# doodle_with_clock5_atmega328_3.net
KiCad netlist of a schematic drawn in EAGLE
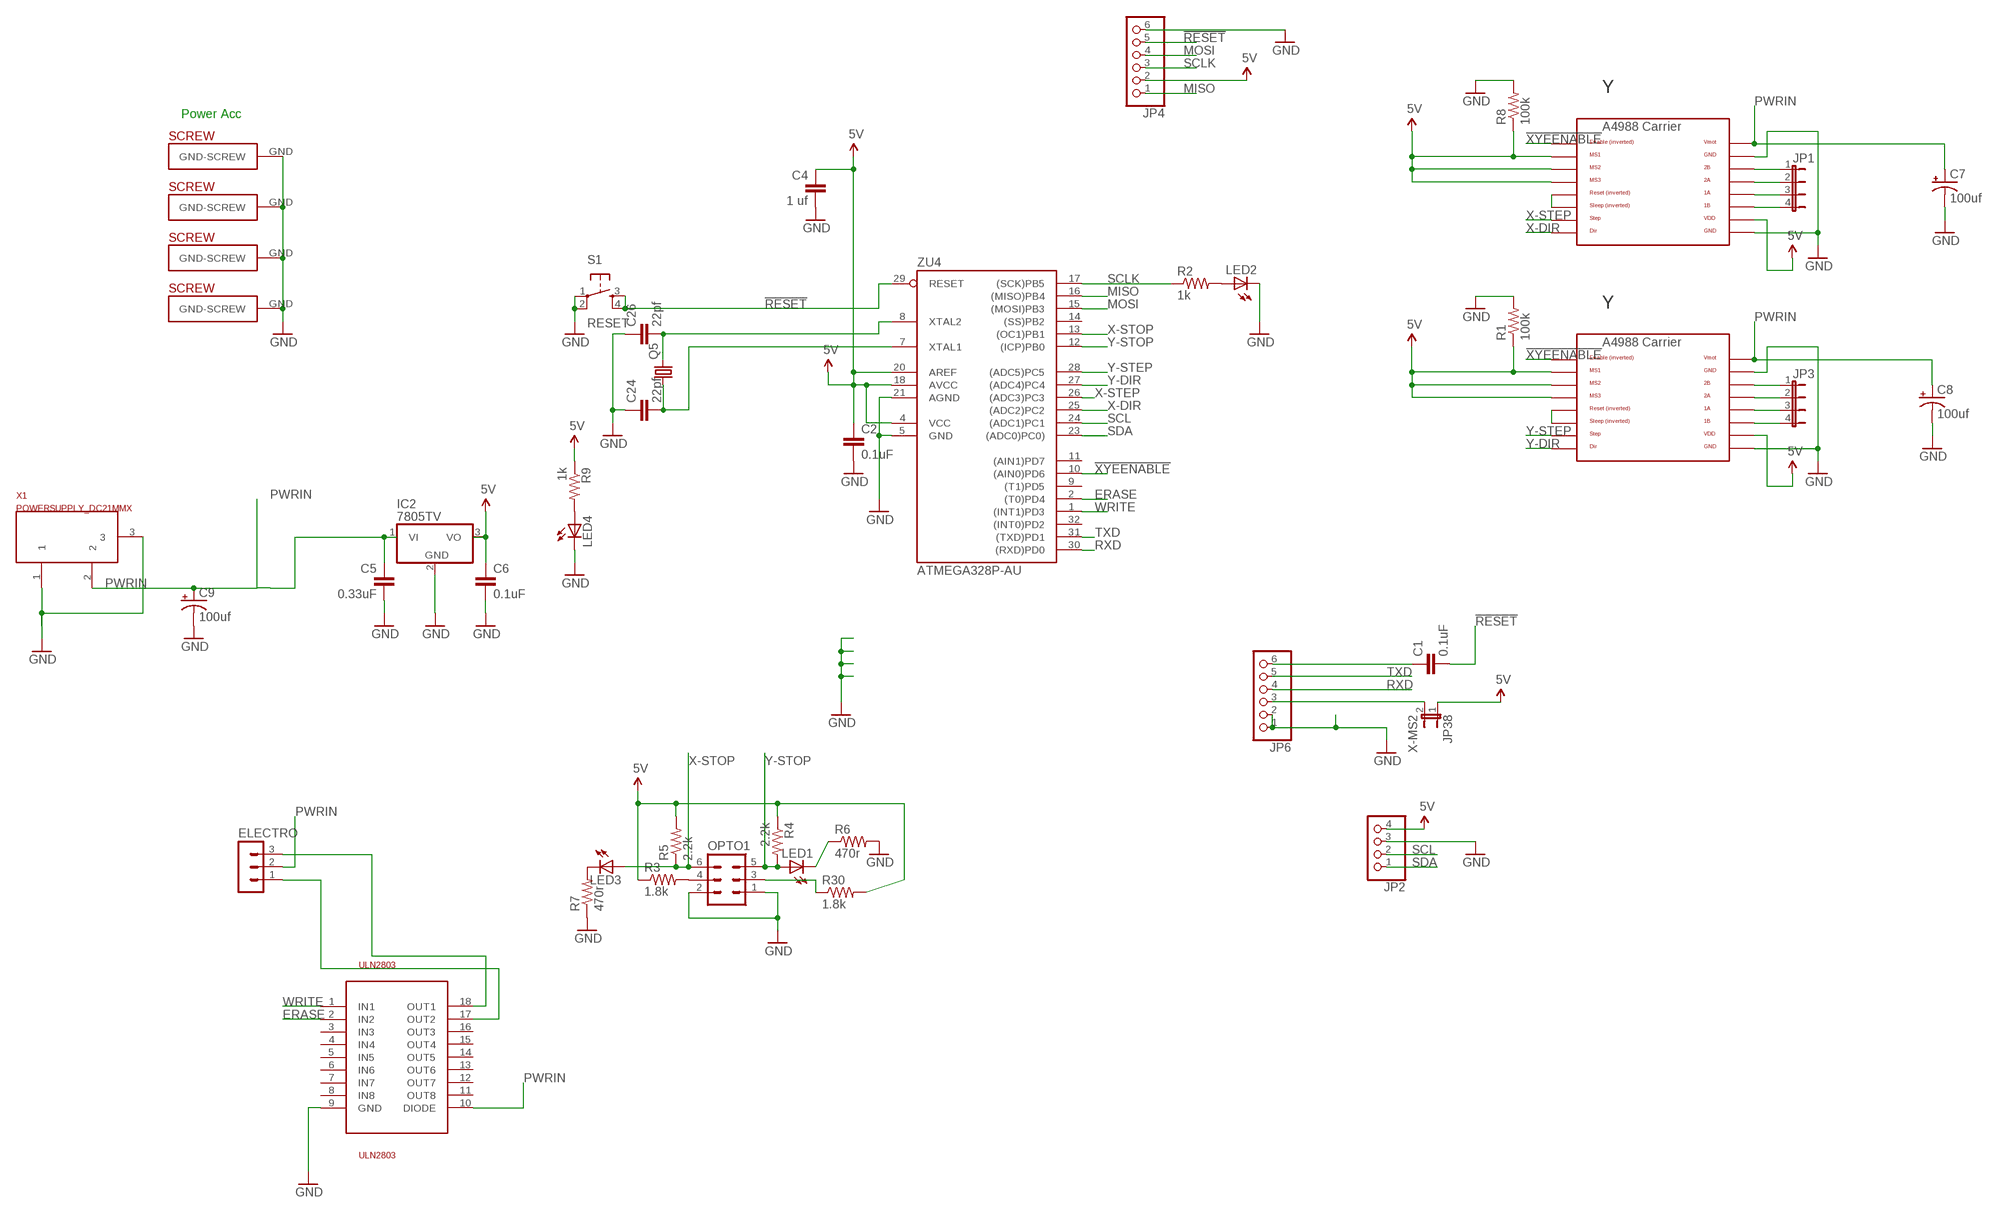
[diagram p0: schematic, sheet 1, part 1 of 2]
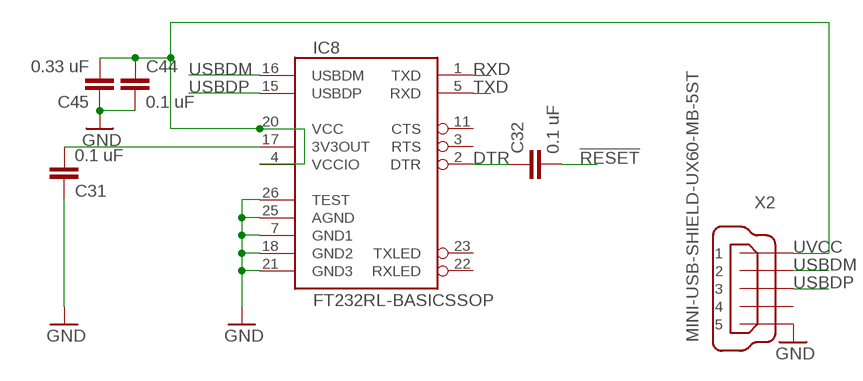
[diagram p1: schematic, sheet 1, part 2 of 2]

(export (version "E")
  (design (tool "Eeschema 10.0.6"))
  (components
    (comp (ref "C1")
      (value "0.1uF")
      (footprint "eagle-import:0805")
      (libsource (lib "eagle-import") (part "CAP0805"))
    )
    (comp (ref "C2")
      (value "0.1uF")
      (footprint "eagle-import:0805")
      (libsource (lib "eagle-import") (part "CAP0805"))
    )
    (comp (ref "C4")
      (value "1 uf")
      (footprint "eagle-import:0805")
      (libsource (lib "eagle-import") (part "CAP0805"))
    )
    (comp (ref "C5")
      (value "0.33uF")
      (footprint "eagle-import:CAP-PTH-SMALL2")
      (libsource (lib "eagle-import") (part "CAPPTH2"))
    )
    (comp (ref "C6")
      (value "0.1uF")
      (footprint "eagle-import:CAP-PTH-SMALL2")
      (libsource (lib "eagle-import") (part "CAPPTH2"))
    )
    (comp (ref "C7")
      (value "100uf")
      (footprint "eagle-import:CPOL-RADIAL-100UF-25V")
      (libsource (lib "eagle-import") (part "CAP_POLPTH1"))
    )
    (comp (ref "C8")
      (value "100uf")
      (footprint "eagle-import:CPOL-RADIAL-100UF-25V")
      (libsource (lib "eagle-import") (part "CAP_POLPTH1"))
    )
    (comp (ref "C9")
      (value "100uf")
      (footprint "eagle-import:CPOL-RADIAL-100UF-25V")
      (libsource (lib "eagle-import") (part "CAP_POLPTH1"))
    )
    (comp (ref "C24")
      (value "22pf")
      (footprint "eagle-import:0805")
      (libsource (lib "eagle-import") (part "CAP0805"))
    )
    (comp (ref "C26")
      (value "22pf")
      (footprint "eagle-import:0805")
      (libsource (lib "eagle-import") (part "CAP0805"))
    )
    (comp (ref "C31")
      (value "0.1 uF")
      (footprint "eagle-import:C1206")
      (libsource (lib "eagle-import") (part "C-EUC1206"))
    )
    (comp (ref "C32")
      (value "0.1 uF")
      (footprint "eagle-import:C1206")
      (libsource (lib "eagle-import") (part "C-EUC1206"))
    )
    (comp (ref "C44")
      (value "0.1 uF")
      (footprint "eagle-import:C1206")
      (libsource (lib "eagle-import") (part "C-EUC1206"))
    )
    (comp (ref "C45")
      (value "0.33 uF")
      (footprint "eagle-import:C1206")
      (libsource (lib "eagle-import") (part "C-EUC1206"))
    )
    (comp (ref "ELECTRO")
      (value "MA03-1")
      (footprint "eagle-import:MA03-1")
      (libsource (lib "eagle-import") (part "MA03-1"))
    )
    (comp (ref "IC2")
      (value "7805TV")
      (footprint "eagle-import:TO220V")
      (libsource (lib "eagle-import") (part "78TV05"))
    )
    (comp (ref "IC8")
      (value "FT232RL-BASICSSOP")
      (footprint "eagle-import:SSOP28DB")
      (libsource (lib "eagle-import") (part "FT232RL-BASICSSOP"))
    )
    (comp (ref "JP1")
      (value "JP4E")
      (footprint "eagle-import:JP4")
      (libsource (lib "eagle-import") (part "JP4E"))
    )
    (comp (ref "JP2")
      (value "PINHD-1X4")
      (footprint "eagle-import:1X04")
      (libsource (lib "eagle-import") (part "PINHD-1X4"))
    )
    (comp (ref "JP3")
      (value "JP4E")
      (footprint "eagle-import:JP4")
      (libsource (lib "eagle-import") (part "JP4E"))
    )
    (comp (ref "JP4")
      (value "PINHD-1X6/90")
      (footprint "eagle-import:1X06_90")
      (libsource (lib "eagle-import") (part "PINHD-1X6/90"))
    )
    (comp (ref "JP6")
      (value "PINHD-1X6")
      (footprint "eagle-import:1X06")
      (libsource (lib "eagle-import") (part "PINHD-1X6"))
    )
    (comp (ref "JP38")
      (value "X-MS2")
      (footprint "eagle-import:1X02")
      (libsource (lib "eagle-import") (part "JUMPER-2PTH"))
    )
    (comp (ref "LED1")
      (value "LEDCHIPLED_0805")
      (footprint "eagle-import:CHIPLED_0805")
      (libsource (lib "eagle-import") (part "LEDCHIPLED_0805"))
    )
    (comp (ref "LED2")
      (value "LEDCHIPLED_0805")
      (footprint "eagle-import:CHIPLED_0805")
      (libsource (lib "eagle-import") (part "LEDCHIPLED_0805"))
    )
    (comp (ref "LED3")
      (value "LEDCHIPLED_0805")
      (footprint "eagle-import:CHIPLED_0805")
      (libsource (lib "eagle-import") (part "LEDCHIPLED_0805"))
    )
    (comp (ref "LED4")
      (value "LEDCHIPLED_0805")
      (footprint "eagle-import:CHIPLED_0805")
      (libsource (lib "eagle-import") (part "LEDCHIPLED_0805"))
    )
    (comp (ref "OPTO1")
      (value "MA03-2")
      (footprint "eagle-import:MA03-2")
      (libsource (lib "eagle-import") (part "MA03-2"))
    )
    (comp (ref "Q5")
      (value "CRYSTALHC49S")
      (footprint "eagle-import:HC49_S")
      (libsource (lib "eagle-import") (part "CRYSTALHC49S"))
    )
    (comp (ref "R1")
      (value "100k")
      (footprint "eagle-import:0207_7")
      (libsource (lib "eagle-import") (part "R-US_0207/7"))
    )
    (comp (ref "R2")
      (value "1k")
      (footprint "eagle-import:R0805")
      (libsource (lib "eagle-import") (part "resistor_R-US_R0805"))
    )
    (comp (ref "R3")
      (value "1.8k")
      (footprint "eagle-import:R0805")
      (libsource (lib "eagle-import") (part "resistor_R-US_R0805"))
    )
    (comp (ref "R4")
      (value "2.2k")
      (footprint "eagle-import:R0805")
      (libsource (lib "eagle-import") (part "resistor_R-US_R0805"))
    )
    (comp (ref "R5")
      (value "2.2k")
      (footprint "eagle-import:R0805")
      (libsource (lib "eagle-import") (part "resistor_R-US_R0805"))
    )
    (comp (ref "R6")
      (value "470r")
      (footprint "eagle-import:R0805")
      (libsource (lib "eagle-import") (part "resistor_R-US_R0805"))
    )
    (comp (ref "R7")
      (value "470r")
      (footprint "eagle-import:R0805")
      (libsource (lib "eagle-import") (part "resistor_R-US_R0805"))
    )
    (comp (ref "R8")
      (value "100k")
      (footprint "eagle-import:0207_7")
      (libsource (lib "eagle-import") (part "R-US_0207/7"))
    )
    (comp (ref "R9")
      (value "1k")
      (footprint "eagle-import:R0805")
      (libsource (lib "eagle-import") (part "resistor_R-US_R0805"))
    )
    (comp (ref "R30")
      (value "1.8k")
      (footprint "eagle-import:R0603")
      (libsource (lib "eagle-import") (part "resistor_R-US_R0603"))
    )
    (comp (ref "S1")
      (value "RESET")
      (footprint "eagle-import:TACTILE-PTH")
      (libsource (lib "eagle-import") (part "TAC_SWITCHPTH"))
    )
    (comp (ref "U$1")
      (value "A4988BREAKOUT")
      (footprint "eagle-import:A4988BREAKOUT")
      (libsource (lib "eagle-import") (part "A4988BREAKOUT"))
    )
    (comp (ref "U$7")
      (value "A4988BREAKOUT")
      (footprint "eagle-import:A4988BREAKOUT")
      (libsource (lib "eagle-import") (part "A4988BREAKOUT"))
    )
    (comp (ref "U$14")
      (value "PLATED-SCREW")
      (footprint "eagle-import:PLATEDSCREW")
      (libsource (lib "eagle-import") (part "PLATED-SCREW"))
    )
    (comp (ref "U$17")
      (value "PLATED-SCREW")
      (footprint "eagle-import:PLATEDSCREW")
      (libsource (lib "eagle-import") (part "PLATED-SCREW"))
    )
    (comp (ref "U$18")
      (value "PLATED-SCREW")
      (footprint "eagle-import:PLATEDSCREW")
      (libsource (lib "eagle-import") (part "PLATED-SCREW"))
    )
    (comp (ref "U$38")
      (value "PLATED-SCREW")
      (footprint "eagle-import:PLATEDSCREW")
      (libsource (lib "eagle-import") (part "PLATED-SCREW"))
    )
    (comp (ref "ULN2803")
      (value "ULN2803")
      (footprint "eagle-import:SO18L")
      (libsource (lib "eagle-import") (part "ULN2803"))
    )
    (comp (ref "X1")
      (value "POWERSUPPLY_DC21MMX")
      (footprint "eagle-import:POWERSUPPLY_DC-21MM")
      (libsource (lib "eagle-import") (part "POWERSUPPLY_DC21MMX"))
    )
    (comp (ref "X2")
      (value "MINI-USB-SHIELD-UX60-MB-5ST")
      (footprint "eagle-import:UX60-MB-5ST")
      (libsource (lib "eagle-import") (part "MINI-USB-SHIELD-UX60-MB-5ST"))
    )
    (comp (ref "ZU4")
      (value "ATMEGA328P-AU")
      (footprint "eagle-import:TQFP32-08")
      (libsource (lib "eagle-import") (part "ATMEGA328P-AU"))
    )
  )
  (nets
    (net (code "1") (name "/DTR") (class "Default")
      (node (ref "C32") (pin "1") (pinfunction "1_1") (pintype "passive"))
      (node (ref "IC8") (pin "2") (pinfunction "DTR_2") (pintype "bidirectional"))
    )
    (net (code "2") (name "/ERASE") (class "Default")
      (node (ref "ULN2803") (pin "2") (pinfunction "IN2_2") (pintype "input"))
      (node (ref "ZU4") (pin "2") (pinfunction "(T0)PD4_2") (pintype "bidirectional"))
    )
    (net (code "3") (name "/MISO") (class "Default")
      (node (ref "JP4") (pin "1") (pinfunction "1_1") (pintype "passive"))
      (node (ref "ZU4") (pin "16") (pinfunction "(MISO)PB4_16") (pintype "bidirectional"))
    )
    (net (code "4") (name "/MOSI") (class "Default")
      (node (ref "JP4") (pin "4") (pinfunction "4_4") (pintype "passive"))
      (node (ref "ZU4") (pin "15") (pinfunction "(MOSI)PB3_15") (pintype "bidirectional"))
    )
    (net (code "5") (name "/PWRIN") (class "Default")
      (node (ref "C5") (pin "1") (pinfunction "1_1") (pintype "passive"))
      (node (ref "C7") (pin "1") (pinfunction "+_1") (pintype "passive"))
      (node (ref "C8") (pin "1") (pinfunction "+_1") (pintype "passive"))
      (node (ref "C9") (pin "1") (pinfunction "+_1") (pintype "passive"))
      (node (ref "ELECTRO") (pin "2") (pinfunction "2_2") (pintype "passive"))
      (node (ref "IC2") (pin "1") (pinfunction "VI_1") (pintype "input"))
      (node (ref "U$1") (pin "VMOT") (pinfunction "VMOT_VMOT") (pintype "power_in"))
      (node (ref "U$7") (pin "VMOT") (pinfunction "VMOT_VMOT") (pintype "power_in"))
      (node (ref "ULN2803") (pin "10") (pinfunction "DIODE_10") (pintype "power_in"))
      (node (ref "X1") (pin "2") (pinfunction "2_2") (pintype "power_in"))
    )
    (net (code "6") (name "/RXD") (class "Default")
      (node (ref "IC8") (pin "1") (pinfunction "TXD_1") (pintype "output"))
      (node (ref "JP6") (pin "4") (pinfunction "4_4") (pintype "passive"))
      (node (ref "ZU4") (pin "30") (pinfunction "(RXD)PD0_30") (pintype "bidirectional"))
    )
    (net (code "7") (name "/SCL") (class "Default")
      (node (ref "JP2") (pin "2") (pinfunction "2_2") (pintype "passive"))
      (node (ref "ZU4") (pin "24") (pinfunction "(ADC1)PC1_24") (pintype "bidirectional"))
    )
    (net (code "8") (name "/SCLK") (class "Default")
      (node (ref "JP4") (pin "3") (pinfunction "3_3") (pintype "passive"))
      (node (ref "R2") (pin "1") (pinfunction "1_1") (pintype "passive"))
      (node (ref "ZU4") (pin "17") (pinfunction "(SCK)PB5_17") (pintype "bidirectional"))
    )
    (net (code "9") (name "/SDA") (class "Default")
      (node (ref "JP2") (pin "1") (pinfunction "1_1") (pintype "passive"))
      (node (ref "ZU4") (pin "23") (pinfunction "(ADC0)PC0)_23") (pintype "bidirectional"))
    )
    (net (code "10") (name "/TXD") (class "Default")
      (node (ref "IC8") (pin "5") (pinfunction "RXD_5") (pintype "input"))
      (node (ref "JP6") (pin "5") (pinfunction "5_5") (pintype "passive"))
      (node (ref "ZU4") (pin "31") (pinfunction "(TXD)PD1_31") (pintype "bidirectional"))
    )
    (net (code "11") (name "/USBDM") (class "Default")
      (node (ref "IC8") (pin "16") (pinfunction "USBDM_16") (pintype "bidirectional"))
      (node (ref "X2") (pin "2") (pinfunction "2_2") (pintype "input"))
    )
    (net (code "12") (name "/USBDP") (class "Default")
      (node (ref "IC8") (pin "15") (pinfunction "USBDP_15") (pintype "bidirectional"))
      (node (ref "X2") (pin "3") (pinfunction "3_3") (pintype "input"))
    )
    (net (code "13") (name "/UVCC") (class "Default")
      (node (ref "C44") (pin "1") (pinfunction "1_1") (pintype "passive"))
      (node (ref "C45") (pin "2") (pinfunction "2_2") (pintype "passive"))
      (node (ref "IC8") (pin "20") (pinfunction "VCC_20") (pintype "power_in"))
      (node (ref "IC8") (pin "4") (pinfunction "VCCIO_4") (pintype "power_in"))
      (node (ref "X2") (pin "1") (pinfunction "1_1") (pintype "input"))
    )
    (net (code "14") (name "/WRITE") (class "Default")
      (node (ref "ULN2803") (pin "1") (pinfunction "IN1_1") (pintype "input"))
      (node (ref "ZU4") (pin "1") (pinfunction "(INT1)PD3_1") (pintype "bidirectional"))
    )
    (net (code "15") (name "/X-DIR") (class "Default")
      (node (ref "U$7") (pin "DIR") (pinfunction "DIR_DIR") (pintype "input"))
      (node (ref "ZU4") (pin "25") (pinfunction "(ADC2)PC2_25") (pintype "bidirectional"))
    )
    (net (code "16") (name "/X-STEP") (class "Default")
      (node (ref "U$7") (pin "STEP") (pinfunction "STEP_STEP") (pintype "input"))
      (node (ref "ZU4") (pin "26") (pinfunction "(ADC3)PC3_26") (pintype "bidirectional"))
    )
    (net (code "17") (name "/X-STOP") (class "Default")
      (node (ref "LED3") (pin "A") (pinfunction "A_A") (pintype "passive"))
      (node (ref "OPTO1") (pin "6") (pinfunction "6_6") (pintype "passive"))
      (node (ref "R5") (pin "1") (pinfunction "1_1") (pintype "passive"))
      (node (ref "ZU4") (pin "13") (pinfunction "(OC1)PB1_13") (pintype "bidirectional"))
    )
    (net (code "18") (name "/Y-DIR") (class "Default")
      (node (ref "U$1") (pin "DIR") (pinfunction "DIR_DIR") (pintype "input"))
      (node (ref "ZU4") (pin "27") (pinfunction "(ADC4)PC4_27") (pintype "bidirectional"))
    )
    (net (code "19") (name "/Y-STEP") (class "Default")
      (node (ref "U$1") (pin "STEP") (pinfunction "STEP_STEP") (pintype "input"))
      (node (ref "ZU4") (pin "28") (pinfunction "(ADC5)PC5_28") (pintype "bidirectional"))
    )
    (net (code "20") (name "/Y-STOP") (class "Default")
      (node (ref "LED1") (pin "A") (pinfunction "A_A") (pintype "passive"))
      (node (ref "OPTO1") (pin "5") (pinfunction "5_5") (pintype "passive"))
      (node (ref "R4") (pin "2") (pinfunction "2_2") (pintype "passive"))
      (node (ref "ZU4") (pin "12") (pinfunction "(ICP)PB0_12") (pintype "bidirectional"))
    )
    (net (code "21") (name "/~{RESET}") (class "Default")
      (node (ref "C1") (pin "2") (pinfunction "2_2") (pintype "passive"))
      (node (ref "C32") (pin "2") (pinfunction "2_2") (pintype "passive"))
      (node (ref "JP4") (pin "5") (pinfunction "5_5") (pintype "passive"))
      (node (ref "S1") (pin "3") (pinfunction "3_3") (pintype "passive"))
      (node (ref "S1") (pin "4") (pinfunction "4_4") (pintype "passive"))
      (node (ref "ZU4") (pin "29") (pinfunction "RESET_29") (pintype "input"))
    )
    (net (code "22") (name "/~{XYEENABLE}") (class "Default")
      (node (ref "U$1") (pin "EN") (pinfunction "EN_EN") (pintype "input"))
      (node (ref "U$7") (pin "EN") (pinfunction "EN_EN") (pintype "input"))
      (node (ref "ZU4") (pin "10") (pinfunction "(AIN0)PD6_10") (pintype "bidirectional"))
    )
    (net (code "23") (name "5V") (class "Default")
      (node (ref "C2") (pin "1") (pinfunction "1_1") (pintype "passive"))
      (node (ref "C4") (pin "1") (pinfunction "1_1") (pintype "passive"))
      (node (ref "C6") (pin "1") (pinfunction "1_1") (pintype "passive"))
      (node (ref "IC2") (pin "3") (pinfunction "VO_3") (pintype "passive"))
      (node (ref "JP2") (pin "4") (pinfunction "4_4") (pintype "passive"))
      (node (ref "JP38") (pin "1") (pinfunction "1_1") (pintype "passive"))
      (node (ref "JP4") (pin "2") (pinfunction "2_2") (pintype "passive"))
      (node (ref "R1") (pin "1") (pinfunction "1_1") (pintype "passive"))
      (node (ref "R3") (pin "1") (pinfunction "1_1") (pintype "passive"))
      (node (ref "R30") (pin "2") (pinfunction "2_2") (pintype "passive"))
      (node (ref "R4") (pin "1") (pinfunction "1_1") (pintype "passive"))
      (node (ref "R5") (pin "2") (pinfunction "2_2") (pintype "passive"))
      (node (ref "R8") (pin "1") (pinfunction "1_1") (pintype "passive"))
      (node (ref "R9") (pin "1") (pinfunction "1_1") (pintype "passive"))
      (node (ref "U$1") (pin "MS1") (pinfunction "MS1_MS1") (pintype "input"))
      (node (ref "U$1") (pin "MS2") (pinfunction "MS2_MS2") (pintype "input"))
      (node (ref "U$1") (pin "MS3") (pinfunction "MS3_MS3") (pintype "input"))
      (node (ref "U$1") (pin "VDD") (pinfunction "VDD_VDD") (pintype "power_in"))
      (node (ref "U$7") (pin "MS1") (pinfunction "MS1_MS1") (pintype "input"))
      (node (ref "U$7") (pin "MS2") (pinfunction "MS2_MS2") (pintype "input"))
      (node (ref "U$7") (pin "MS3") (pinfunction "MS3_MS3") (pintype "input"))
      (node (ref "U$7") (pin "VDD") (pinfunction "VDD_VDD") (pintype "power_in"))
      (node (ref "ZU4") (pin "18") (pinfunction "AVCC_18") (pintype "power_in"))
      (node (ref "ZU4") (pin "20") (pinfunction "AREF_20") (pintype "passive"))
      (node (ref "ZU4") (pin "4") (pinfunction "VCC_4") (pintype "power_in"))
    )
    (net (code "24") (name "GND") (class "Default")
      (node (ref "C2") (pin "2") (pinfunction "2_2") (pintype "passive"))
      (node (ref "C24") (pin "1") (pinfunction "1_1") (pintype "passive"))
      (node (ref "C26") (pin "1") (pinfunction "1_1") (pintype "passive"))
      (node (ref "C31") (pin "1") (pinfunction "1_1") (pintype "passive"))
      (node (ref "C4") (pin "2") (pinfunction "2_2") (pintype "passive"))
      (node (ref "C44") (pin "2") (pinfunction "2_2") (pintype "passive"))
      (node (ref "C45") (pin "1") (pinfunction "1_1") (pintype "passive"))
      (node (ref "C5") (pin "2") (pinfunction "2_2") (pintype "passive"))
      (node (ref "C6") (pin "2") (pinfunction "2_2") (pintype "passive"))
      (node (ref "C7") (pin "2") (pinfunction "-_2") (pintype "passive"))
      (node (ref "C8") (pin "2") (pinfunction "-_2") (pintype "passive"))
      (node (ref "C9") (pin "2") (pinfunction "-_2") (pintype "passive"))
      (node (ref "IC2") (pin "2") (pinfunction "GND_2") (pintype "passive"))
      (node (ref "IC8") (pin "18") (pinfunction "GND2_18") (pintype "power_in"))
      (node (ref "IC8") (pin "21") (pinfunction "GND3_21") (pintype "power_in"))
      (node (ref "IC8") (pin "25") (pinfunction "AGND_25") (pintype "power_in"))
      (node (ref "IC8") (pin "26") (pinfunction "TEST_26") (pintype "input"))
      (node (ref "IC8") (pin "7") (pinfunction "GND1_7") (pintype "power_in"))
      (node (ref "JP2") (pin "3") (pinfunction "3_3") (pintype "passive"))
      (node (ref "JP4") (pin "6") (pinfunction "6_6") (pintype "passive"))
      (node (ref "JP6") (pin "1") (pinfunction "1_1") (pintype "passive"))
      (node (ref "JP6") (pin "2") (pinfunction "2_2") (pintype "passive"))
      (node (ref "LED2") (pin "C") (pinfunction "C_C") (pintype "passive"))
      (node (ref "LED4") (pin "C") (pinfunction "C_C") (pintype "passive"))
      (node (ref "OPTO1") (pin "1") (pinfunction "1_1") (pintype "passive"))
      (node (ref "OPTO1") (pin "2") (pinfunction "2_2") (pintype "passive"))
      (node (ref "R1") (pin "2") (pinfunction "2_2") (pintype "passive"))
      (node (ref "R6") (pin "2") (pinfunction "2_2") (pintype "passive"))
      (node (ref "R7") (pin "1") (pinfunction "1_1") (pintype "passive"))
      (node (ref "R8") (pin "2") (pinfunction "2_2") (pintype "passive"))
      (node (ref "S1") (pin "1") (pinfunction "1_1") (pintype "passive"))
      (node (ref "S1") (pin "2") (pinfunction "2_2") (pintype "passive"))
      (node (ref "U$1") (pin "GND") (pinfunction "GND_GND") (pintype "power_in"))
      (node (ref "U$1") (pin "GND@0") (pinfunction "GND_GND@0") (pintype "power_in"))
      (node (ref "U$14") (pin "GND") (pinfunction "GND-SCREW_GND") (pintype "bidirectional"))
      (node (ref "U$17") (pin "GND") (pinfunction "GND-SCREW_GND") (pintype "bidirectional"))
      (node (ref "U$18") (pin "GND") (pinfunction "GND-SCREW_GND") (pintype "bidirectional"))
      (node (ref "U$38") (pin "GND") (pinfunction "GND-SCREW_GND") (pintype "bidirectional"))
      (node (ref "U$7") (pin "GND") (pinfunction "GND_GND") (pintype "power_in"))
      (node (ref "U$7") (pin "GND@0") (pinfunction "GND_GND@0") (pintype "power_in"))
      (node (ref "ULN2803") (pin "9") (pinfunction "GND_9") (pintype "power_in"))
      (node (ref "X1") (pin "1") (pinfunction "1_1") (pintype "power_in"))
      (node (ref "X1") (pin "3") (pinfunction "3_3") (pintype "power_in"))
      (node (ref "X2") (pin "5") (pinfunction "5_5") (pintype "input"))
      (node (ref "ZU4") (pin "21") (pinfunction "AGND_21") (pintype "power_in"))
      (node (ref "ZU4") (pin "5") (pinfunction "GND_5") (pintype "power_in"))
    )
    (net (code "25") (name "Net-(C1-Pad1)") (class "Default")
      (node (ref "C1") (pin "1") (pinfunction "1_1") (pintype "passive"))
      (node (ref "JP6") (pin "6") (pinfunction "6_6") (pintype "passive"))
    )
    (net (code "26") (name "Net-(IC8-3V3OUT)") (class "Default")
      (node (ref "C31") (pin "2") (pinfunction "2_2") (pintype "passive"))
      (node (ref "IC8") (pin "17") (pinfunction "3V3OUT_17") (pintype "output"))
    )
    (net (code "27") (name "Net-(JP1-Pad1)") (class "Default")
      (node (ref "JP1") (pin "1") (pinfunction "1_1") (pintype "passive"))
      (node (ref "U$7") (pin "2B") (pinfunction "2B_2B") (pintype "output"))
    )
    (net (code "28") (name "Net-(JP1-Pad2)") (class "Default")
      (node (ref "JP1") (pin "2") (pinfunction "2_2") (pintype "passive"))
      (node (ref "U$7") (pin "2A") (pinfunction "2A_2A") (pintype "output"))
    )
    (net (code "29") (name "Net-(JP1-Pad3)") (class "Default")
      (node (ref "JP1") (pin "3") (pinfunction "3_3") (pintype "passive"))
      (node (ref "U$7") (pin "1A") (pinfunction "1A_1A") (pintype "output"))
    )
    (net (code "30") (name "Net-(JP1-Pad4)") (class "Default")
      (node (ref "JP1") (pin "4") (pinfunction "4_4") (pintype "passive"))
      (node (ref "U$7") (pin "1B") (pinfunction "1B_1B") (pintype "output"))
    )
    (net (code "31") (name "Net-(JP3-Pad1)") (class "Default")
      (node (ref "JP3") (pin "1") (pinfunction "1_1") (pintype "passive"))
      (node (ref "U$1") (pin "2B") (pinfunction "2B_2B") (pintype "output"))
    )
    (net (code "32") (name "Net-(JP3-Pad2)") (class "Default")
      (node (ref "JP3") (pin "2") (pinfunction "2_2") (pintype "passive"))
      (node (ref "U$1") (pin "2A") (pinfunction "2A_2A") (pintype "output"))
    )
    (net (code "33") (name "Net-(JP3-Pad3)") (class "Default")
      (node (ref "JP3") (pin "3") (pinfunction "3_3") (pintype "passive"))
      (node (ref "U$1") (pin "1A") (pinfunction "1A_1A") (pintype "output"))
    )
    (net (code "34") (name "Net-(JP3-Pad4)") (class "Default")
      (node (ref "JP3") (pin "4") (pinfunction "4_4") (pintype "passive"))
      (node (ref "U$1") (pin "1B") (pinfunction "1B_1B") (pintype "output"))
    )
    (net (code "35") (name "Net-(JP38-Pad2)") (class "Default")
      (node (ref "JP38") (pin "2") (pinfunction "2_2") (pintype "passive"))
      (node (ref "JP6") (pin "3") (pinfunction "3_3") (pintype "passive"))
    )
    (net (code "36") (name "Net-(LED1-PadC)") (class "Default")
      (node (ref "LED1") (pin "C") (pinfunction "C_C") (pintype "passive"))
      (node (ref "R6") (pin "1") (pinfunction "1_1") (pintype "passive"))
    )
    (net (code "37") (name "Net-(LED2-PadA)") (class "Default")
      (node (ref "LED2") (pin "A") (pinfunction "A_A") (pintype "passive"))
      (node (ref "R2") (pin "2") (pinfunction "2_2") (pintype "passive"))
    )
    (net (code "38") (name "Net-(LED3-PadC)") (class "Default")
      (node (ref "LED3") (pin "C") (pinfunction "C_C") (pintype "passive"))
      (node (ref "R7") (pin "2") (pinfunction "2_2") (pintype "passive"))
    )
    (net (code "39") (name "Net-(LED4-PadA)") (class "Default")
      (node (ref "LED4") (pin "A") (pinfunction "A_A") (pintype "passive"))
      (node (ref "R9") (pin "2") (pinfunction "2_2") (pintype "passive"))
    )
    (net (code "40") (name "Net-(OPTO1-Pad3)") (class "Default")
      (node (ref "OPTO1") (pin "3") (pinfunction "3_3") (pintype "passive"))
      (node (ref "R30") (pin "1") (pinfunction "1_1") (pintype "passive"))
    )
    (net (code "41") (name "Net-(OPTO1-Pad4)") (class "Default")
      (node (ref "OPTO1") (pin "4") (pinfunction "4_4") (pintype "passive"))
      (node (ref "R3") (pin "2") (pinfunction "2_2") (pintype "passive"))
    )
    (net (code "42") (name "Net-(U$1-SLEEP)") (class "Default")
      (node (ref "U$1") (pin "RST") (pinfunction "RST_RST") (pintype "input"))
      (node (ref "U$1") (pin "SLP") (pinfunction "SLEEP_SLP") (pintype "input"))
    )
    (net (code "43") (name "Net-(U$7-SLEEP)") (class "Default")
      (node (ref "U$7") (pin "RST") (pinfunction "RST_RST") (pintype "input"))
      (node (ref "U$7") (pin "SLP") (pinfunction "SLEEP_SLP") (pintype "input"))
    )
    (net (code "44") (name "Net-(ULN2803-OUT1)") (class "Default")
      (node (ref "ELECTRO") (pin "3") (pinfunction "3_3") (pintype "passive"))
      (node (ref "ULN2803") (pin "18") (pinfunction "OUT1_18") (pintype "open_collector"))
    )
    (net (code "45") (name "Net-(ULN2803-OUT2)") (class "Default")
      (node (ref "ELECTRO") (pin "1") (pinfunction "1_1") (pintype "passive"))
      (node (ref "ULN2803") (pin "17") (pinfunction "OUT2_17") (pintype "open_collector"))
    )
    (net (code "46") (name "Net-(ZU4-XTAL1)") (class "Default")
      (node (ref "C24") (pin "2") (pinfunction "2_2") (pintype "passive"))
      (node (ref "Q5") (pin "1") (pinfunction "1_1") (pintype "passive"))
      (node (ref "ZU4") (pin "7") (pinfunction "XTAL1_7") (pintype "bidirectional"))
    )
    (net (code "47") (name "Net-(ZU4-XTAL2)") (class "Default")
      (node (ref "C26") (pin "2") (pinfunction "2_2") (pintype "passive"))
      (node (ref "Q5") (pin "2") (pinfunction "2_2") (pintype "passive"))
      (node (ref "ZU4") (pin "8") (pinfunction "XTAL2_8") (pintype "bidirectional"))
    )
    (net (code "48") (name "unconnected-(IC8-CTS-Pad11)") (class "Default")
      (node (ref "IC8") (pin "11") (pinfunction "CTS_11") (pintype "bidirectional"))
    )
    (net (code "49") (name "unconnected-(IC8-RTS-Pad3)") (class "Default")
      (node (ref "IC8") (pin "3") (pinfunction "RTS_3") (pintype "bidirectional"))
    )
    (net (code "50") (name "unconnected-(IC8-RXLED-Pad22)") (class "Default")
      (node (ref "IC8") (pin "22") (pinfunction "RXLED_22") (pintype "bidirectional"))
    )
    (net (code "51") (name "unconnected-(IC8-TXLED-Pad23)") (class "Default")
      (node (ref "IC8") (pin "23") (pinfunction "TXLED_23") (pintype "bidirectional"))
    )
    (net (code "52") (name "unconnected-(ULN2803-IN3-Pad3)") (class "Default")
      (node (ref "ULN2803") (pin "3") (pinfunction "IN3_3") (pintype "input"))
    )
    (net (code "53") (name "unconnected-(ULN2803-IN4-Pad4)") (class "Default")
      (node (ref "ULN2803") (pin "4") (pinfunction "IN4_4") (pintype "input"))
    )
    (net (code "54") (name "unconnected-(ULN2803-IN5-Pad5)") (class "Default")
      (node (ref "ULN2803") (pin "5") (pinfunction "IN5_5") (pintype "input"))
    )
    (net (code "55") (name "unconnected-(ULN2803-IN6-Pad6)") (class "Default")
      (node (ref "ULN2803") (pin "6") (pinfunction "IN6_6") (pintype "input"))
    )
    (net (code "56") (name "unconnected-(ULN2803-IN7-Pad7)") (class "Default")
      (node (ref "ULN2803") (pin "7") (pinfunction "IN7_7") (pintype "input"))
    )
    (net (code "57") (name "unconnected-(ULN2803-IN8-Pad8)") (class "Default")
      (node (ref "ULN2803") (pin "8") (pinfunction "IN8_8") (pintype "input"))
    )
    (net (code "58") (name "unconnected-(ULN2803-OUT3-Pad16)") (class "Default")
      (node (ref "ULN2803") (pin "16") (pinfunction "OUT3_16") (pintype "open_collector"))
    )
    (net (code "59") (name "unconnected-(ULN2803-OUT4-Pad15)") (class "Default")
      (node (ref "ULN2803") (pin "15") (pinfunction "OUT4_15") (pintype "open_collector"))
    )
    (net (code "60") (name "unconnected-(ULN2803-OUT5-Pad14)") (class "Default")
      (node (ref "ULN2803") (pin "14") (pinfunction "OUT5_14") (pintype "open_collector"))
    )
    (net (code "61") (name "unconnected-(ULN2803-OUT6-Pad13)") (class "Default")
      (node (ref "ULN2803") (pin "13") (pinfunction "OUT6_13") (pintype "open_collector"))
    )
    (net (code "62") (name "unconnected-(ULN2803-OUT7-Pad12)") (class "Default")
      (node (ref "ULN2803") (pin "12") (pinfunction "OUT7_12") (pintype "open_collector"))
    )
    (net (code "63") (name "unconnected-(ULN2803-OUT8-Pad11)") (class "Default")
      (node (ref "ULN2803") (pin "11") (pinfunction "OUT8_11") (pintype "open_collector"))
    )
    (net (code "64") (name "unconnected-(X2-Pad4)") (class "Default")
      (node (ref "X2") (pin "4") (pinfunction "4_4") (pintype "input"))
    )
    (net (code "65") (name "unconnected-(ZU4-(AIN1)PD7-Pad11)") (class "Default")
      (node (ref "ZU4") (pin "11") (pinfunction "(AIN1)PD7_11") (pintype "bidirectional"))
    )
    (net (code "66") (name "unconnected-(ZU4-(INT0)PD2-Pad32)") (class "Default")
      (node (ref "ZU4") (pin "32") (pinfunction "(INT0)PD2_32") (pintype "bidirectional"))
    )
    (net (code "67") (name "unconnected-(ZU4-(SS)PB2-Pad14)") (class "Default")
      (node (ref "ZU4") (pin "14") (pinfunction "(SS)PB2_14") (pintype "bidirectional"))
    )
    (net (code "68") (name "unconnected-(ZU4-(T1)PD5-Pad9)") (class "Default")
      (node (ref "ZU4") (pin "9") (pinfunction "(T1)PD5_9") (pintype "bidirectional"))
    )
  )
)
